# BNSK-Rambo-Converters-Device.net
KiCad netlist of a schematic drawn in EAGLE
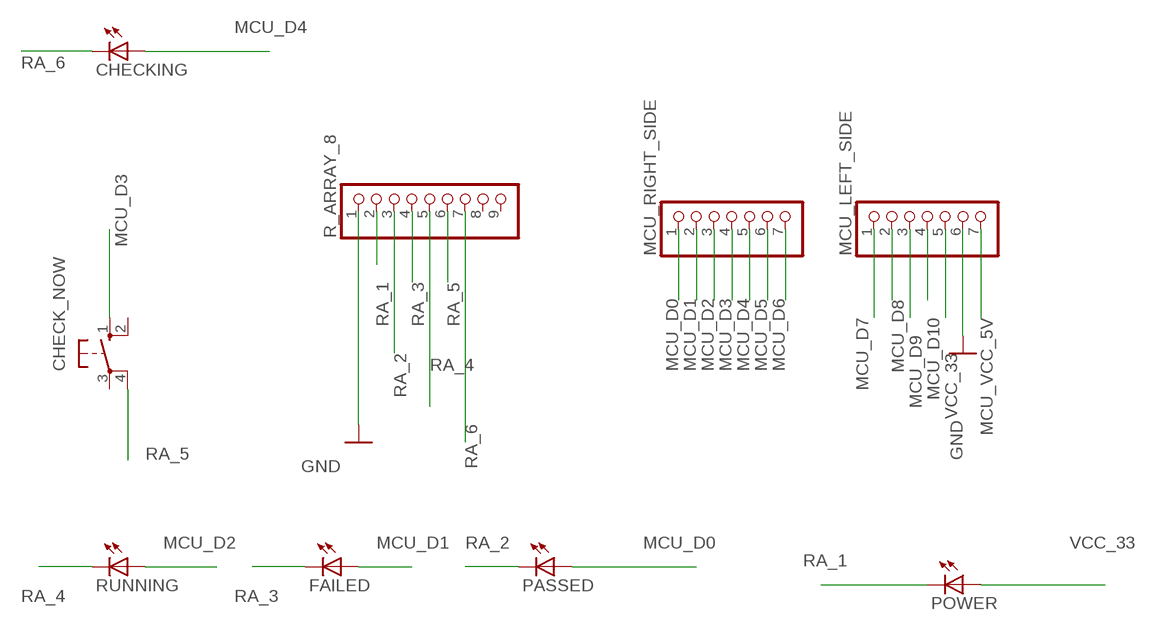
[diagram p0: schematic, sheet 1]

(export (version "E")
  (design (tool "Eeschema 10.0.6"))
  (components
    (comp (ref "CHECKING")
      (value "LEDSMT1206")
      (footprint "eagle-import:1206")
      (libsource (lib "eagle-import") (part "LEDSMT1206"))
    )
    (comp (ref "CHECK_NOW")
      (value "10-XX")
      (footprint "eagle-import:B3F-10XX")
      (fields (field (name "MPN") "B3F-1000"))
      (libsource (lib "eagle-import") (part "10-XX"))
    )
    (comp (ref "FAILED")
      (value "LEDSMT1206")
      (footprint "eagle-import:1206")
      (libsource (lib "eagle-import") (part "LEDSMT1206"))
    )
    (comp (ref "MCU_LEFT_SIDE")
      (value "PINHD-1X7")
      (footprint "eagle-import:1X07")
      (libsource (lib "eagle-import") (part "PINHD-1X7"))
    )
    (comp (ref "MCU_RIGHT_SIDE")
      (value "PINHD-1X7")
      (footprint "eagle-import:1X07")
      (libsource (lib "eagle-import") (part "PINHD-1X7"))
    )
    (comp (ref "PASSED")
      (value "LEDSMT1206")
      (footprint "eagle-import:1206")
      (libsource (lib "eagle-import") (part "LEDSMT1206"))
    )
    (comp (ref "POWER")
      (value "LEDSMT1206")
      (footprint "eagle-import:1206")
      (libsource (lib "eagle-import") (part "LEDSMT1206"))
    )
    (comp (ref "RUNNING")
      (value "LEDSMT1206")
      (footprint "eagle-import:1206")
      (libsource (lib "eagle-import") (part "LEDSMT1206"))
    )
    (comp (ref "R_ARRAY_8")
      (value "PINHD-1X9")
      (footprint "eagle-import:1X09-BIG")
      (libsource (lib "eagle-import") (part "PINHD-1X9"))
    )
  )
  (nets
    (net (code "1") (name "/MCU_D0") (class "Default")
      (node (ref "MCU_RIGHT_SIDE") (pin "1") (pinfunction "1_1") (pintype "passive"))
      (node (ref "PASSED") (pin "A") (pinfunction "A_A") (pintype "passive"))
    )
    (net (code "2") (name "/MCU_D1") (class "Default")
      (node (ref "FAILED") (pin "A") (pinfunction "A_A") (pintype "passive"))
      (node (ref "MCU_RIGHT_SIDE") (pin "2") (pinfunction "2_2") (pintype "passive"))
    )
    (net (code "3") (name "/MCU_D2") (class "Default")
      (node (ref "MCU_RIGHT_SIDE") (pin "3") (pinfunction "3_3") (pintype "passive"))
      (node (ref "RUNNING") (pin "A") (pinfunction "A_A") (pintype "passive"))
    )
    (net (code "4") (name "/MCU_D3") (class "Default")
      (node (ref "CHECK_NOW") (pin "1") (pinfunction "S_1") (pintype "passive"))
      (node (ref "MCU_RIGHT_SIDE") (pin "4") (pinfunction "4_4") (pintype "passive"))
    )
    (net (code "5") (name "/MCU_D4") (class "Default")
      (node (ref "CHECKING") (pin "A") (pinfunction "A_A") (pintype "passive"))
      (node (ref "MCU_RIGHT_SIDE") (pin "5") (pinfunction "5_5") (pintype "passive"))
    )
    (net (code "6") (name "/MCU_D5") (class "Default")
      (node (ref "MCU_RIGHT_SIDE") (pin "6") (pinfunction "6_6") (pintype "passive"))
    )
    (net (code "7") (name "/MCU_D6") (class "Default")
      (node (ref "MCU_RIGHT_SIDE") (pin "7") (pinfunction "7_7") (pintype "passive"))
    )
    (net (code "8") (name "/MCU_D7") (class "Default")
      (node (ref "MCU_LEFT_SIDE") (pin "1") (pinfunction "1_1") (pintype "passive"))
    )
    (net (code "9") (name "/MCU_D8") (class "Default")
      (node (ref "MCU_LEFT_SIDE") (pin "2") (pinfunction "2_2") (pintype "passive"))
    )
    (net (code "10") (name "/MCU_D9") (class "Default")
      (node (ref "MCU_LEFT_SIDE") (pin "3") (pinfunction "3_3") (pintype "passive"))
    )
    (net (code "11") (name "/MCU_D10") (class "Default")
      (node (ref "MCU_LEFT_SIDE") (pin "4") (pinfunction "4_4") (pintype "passive"))
    )
    (net (code "12") (name "/MCU_VCC_5V") (class "Default")
      (node (ref "MCU_LEFT_SIDE") (pin "7") (pinfunction "7_7") (pintype "passive"))
    )
    (net (code "13") (name "/RA_1") (class "Default")
      (node (ref "POWER") (pin "C") (pinfunction "C_C") (pintype "passive"))
      (node (ref "R_ARRAY_8") (pin "2") (pinfunction "2_2") (pintype "passive"))
    )
    (net (code "14") (name "/RA_2") (class "Default")
      (node (ref "PASSED") (pin "C") (pinfunction "C_C") (pintype "passive"))
      (node (ref "R_ARRAY_8") (pin "3") (pinfunction "3_3") (pintype "passive"))
    )
    (net (code "15") (name "/RA_3") (class "Default")
      (node (ref "FAILED") (pin "C") (pinfunction "C_C") (pintype "passive"))
      (node (ref "R_ARRAY_8") (pin "4") (pinfunction "4_4") (pintype "passive"))
    )
    (net (code "16") (name "/RA_4") (class "Default")
      (node (ref "RUNNING") (pin "C") (pinfunction "C_C") (pintype "passive"))
      (node (ref "R_ARRAY_8") (pin "5") (pinfunction "5_5") (pintype "passive"))
    )
    (net (code "17") (name "/RA_5") (class "Default")
      (node (ref "CHECK_NOW") (pin "4") (pinfunction "P1_4") (pintype "passive"))
      (node (ref "R_ARRAY_8") (pin "6") (pinfunction "6_6") (pintype "passive"))
    )
    (net (code "18") (name "/RA_6") (class "Default")
      (node (ref "CHECKING") (pin "C") (pinfunction "C_C") (pintype "passive"))
      (node (ref "R_ARRAY_8") (pin "7") (pinfunction "7_7") (pintype "passive"))
    )
    (net (code "19") (name "/VCC_33") (class "Default")
      (node (ref "MCU_LEFT_SIDE") (pin "5") (pinfunction "5_5") (pintype "passive"))
      (node (ref "POWER") (pin "A") (pinfunction "A_A") (pintype "passive"))
    )
    (net (code "20") (name "GND") (class "Default")
      (node (ref "MCU_LEFT_SIDE") (pin "6") (pinfunction "6_6") (pintype "passive"))
      (node (ref "R_ARRAY_8") (pin "1") (pinfunction "1_1") (pintype "passive"))
    )
    (net (code "21") (name "unconnected-(CHECK_NOW-P-Pad3)") (class "Default")
      (node (ref "CHECK_NOW") (pin "3") (pinfunction "P_3") (pintype "passive"))
    )
    (net (code "22") (name "unconnected-(CHECK_NOW-S1-Pad2)") (class "Default")
      (node (ref "CHECK_NOW") (pin "2") (pinfunction "S1_2") (pintype "passive"))
    )
    (net (code "23") (name "unconnected-(R_ARRAY_8-Pad8)") (class "Default")
      (node (ref "R_ARRAY_8") (pin "8") (pinfunction "8_8") (pintype "passive"))
    )
    (net (code "24") (name "unconnected-(R_ARRAY_8-Pad9)") (class "Default")
      (node (ref "R_ARRAY_8") (pin "9") (pinfunction "9_9") (pintype "passive"))
    )
  )
)
